# eBox_LCD.net
KiCad netlist of a schematic drawn in Altium Designer
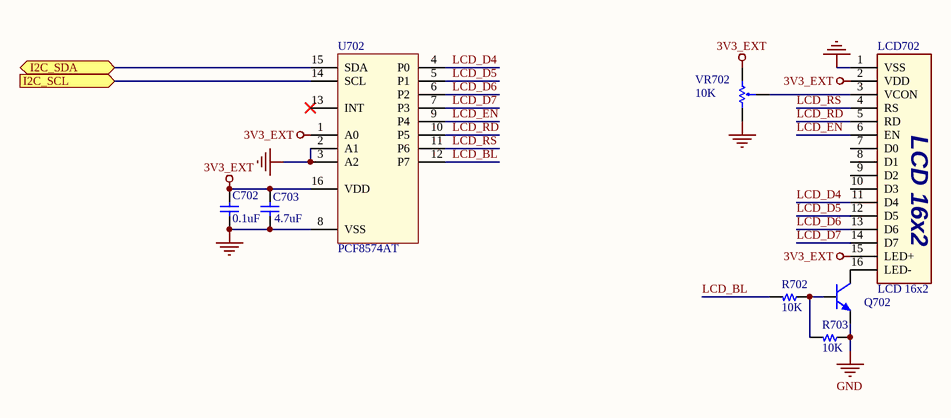
[diagram p0: eBox_LCD.SchDoc]

(export (version "E")
  (design (tool "Eeschema 10.0.6"))
  (components
    (comp (ref "C702")
      (value "0.1uF")
      (footprint "C 0603")
      (description "CAP CER 0.1UF 50V X7R 0603")
      (libsource (lib "chipfc_altium_libs") (part "Capacitor NP"))
    )
    (comp (ref "C703")
      (value "4.7uF")
      (footprint "C 0603")
      (description "CAP CER 4.7UF 50V X7R 0603")
      (libsource (lib "chipfc_altium_libs") (part "Capacitor NP"))
    )
    (comp (ref "LCD702")
      (value "LCD 16x2")
      (footprint "LCD 1602A")
      (description "Character LCD 16x2")
      (libsource (lib "chipfc_altium_libs") (part "LCD 16x2"))
    )
    (comp (ref "Q702")
      (value "LMBT3904LT1G")
      (footprint "SOT-23")
      (description "TRANS NPN 40V 0.2A SMD SOT23-3")
      (libsource (lib "chipfc_altium_libs") (part "Transistor NPN"))
    )
    (comp (ref "R702")
      (value "10K")
      (footprint "R 0603")
      (description "RES SMD 10K OHM 1% 1/10W 0603")
      (libsource (lib "chipfc_altium_libs") (part "Resistor"))
    )
    (comp (ref "R703")
      (value "10K")
      (footprint "R 0603")
      (description "RES SMD 10K OHM 1% 1/10W 0603")
      (libsource (lib "chipfc_altium_libs") (part "Resistor"))
    )
    (comp (ref "U702")
      (value "PCF8574AT")
      (footprint "SO16/PCF8574AT")
      (description "Remote 8-bit I/O expander for I2C-bus with interrupt")
      (fields (field (name "PART NO") "PCF8574AT/3"))
      (libsource (lib "chipfc_altium_libs") (part "PCF8574AT"))
    )
    (comp (ref "VR702")
      (value "10K")
      (footprint "R VAR A 3D")
      (description "Resistor Variable")
      (libsource (lib "chipfc_altium_libs") (part "Resistor Variable"))
    )
  )
  (nets
    (net (code "1") (name "/I2C_SCL") (class "Default")
      (node (ref "U702") (pin "14") (pinfunction "SCL_14") (pintype "passive"))
    )
    (net (code "2") (name "/I2C_SDA") (class "Default")
      (node (ref "U702") (pin "15") (pinfunction "SDA_15") (pintype "passive"))
    )
    (net (code "3") (name "/LCD_BL") (class "Default")
      (node (ref "R702") (pin "2") (pinfunction "2_2") (pintype "passive"))
      (node (ref "U702") (pin "12") (pinfunction "P7_12") (pintype "passive"))
    )
    (net (code "4") (name "/LCD_D4") (class "Default")
      (node (ref "LCD702") (pin "11") (pinfunction "D4_11") (pintype "passive"))
      (node (ref "U702") (pin "4") (pinfunction "P0_4") (pintype "passive"))
    )
    (net (code "5") (name "/LCD_D5") (class "Default")
      (node (ref "LCD702") (pin "12") (pinfunction "D5_12") (pintype "passive"))
      (node (ref "U702") (pin "5") (pinfunction "P1_5") (pintype "passive"))
    )
    (net (code "6") (name "/LCD_D6") (class "Default")
      (node (ref "LCD702") (pin "13") (pinfunction "D6_13") (pintype "passive"))
      (node (ref "U702") (pin "6") (pinfunction "P2_6") (pintype "passive"))
    )
    (net (code "7") (name "/LCD_D7") (class "Default")
      (node (ref "LCD702") (pin "14") (pinfunction "D7_14") (pintype "passive"))
      (node (ref "U702") (pin "7") (pinfunction "P3_7") (pintype "passive"))
    )
    (net (code "8") (name "/LCD_EN") (class "Default")
      (node (ref "LCD702") (pin "6") (pinfunction "EN_6") (pintype "passive"))
      (node (ref "U702") (pin "9") (pinfunction "P4_9") (pintype "passive"))
    )
    (net (code "9") (name "/LCD_RD") (class "Default")
      (node (ref "LCD702") (pin "5") (pinfunction "RD_5") (pintype "passive"))
      (node (ref "U702") (pin "10") (pinfunction "P5_10") (pintype "passive"))
    )
    (net (code "10") (name "/LCD_RS") (class "Default")
      (node (ref "LCD702") (pin "4") (pinfunction "RS_4") (pintype "passive"))
      (node (ref "U702") (pin "11") (pinfunction "P6_11") (pintype "passive"))
    )
    (net (code "11") (name "3V3_EXT") (class "Default")
      (node (ref "C702") (pin "1") (pinfunction "1_1") (pintype "passive"))
      (node (ref "C703") (pin "1") (pinfunction "1_1") (pintype "passive"))
      (node (ref "LCD702") (pin "15") (pinfunction "LED+_15") (pintype "passive"))
      (node (ref "LCD702") (pin "2") (pinfunction "VDD_2") (pintype "passive"))
      (node (ref "U702") (pin "1") (pinfunction "A0_1") (pintype "passive"))
      (node (ref "U702") (pin "16") (pinfunction "VDD_16") (pintype "passive"))
      (node (ref "VR702") (pin "1") (pinfunction "1_1") (pintype "passive"))
    )
    (net (code "12") (name "GND") (class "Default")
      (node (ref "C702") (pin "2") (pinfunction "2_2") (pintype "passive"))
      (node (ref "C703") (pin "2") (pinfunction "2_2") (pintype "passive"))
      (node (ref "LCD702") (pin "1") (pinfunction "VSS_1") (pintype "passive"))
      (node (ref "Q702") (pin "2") (pinfunction "E_2") (pintype "passive"))
      (node (ref "R703") (pin "1") (pinfunction "1_1") (pintype "passive"))
      (node (ref "U702") (pin "2") (pinfunction "A1_2") (pintype "passive"))
      (node (ref "U702") (pin "3") (pinfunction "A2_3") (pintype "passive"))
      (node (ref "U702") (pin "8") (pinfunction "VSS_8") (pintype "passive"))
      (node (ref "VR702") (pin "3") (pinfunction "3_3") (pintype "passive"))
    )
    (net (code "13") (name "Net-(LCD702-LED-)") (class "Default")
      (node (ref "LCD702") (pin "16") (pinfunction "LED-_16") (pintype "passive"))
      (node (ref "Q702") (pin "3") (pinfunction "C_3") (pintype "passive"))
    )
    (net (code "14") (name "Net-(LCD702-VCON)") (class "Default")
      (node (ref "LCD702") (pin "3") (pinfunction "VCON_3") (pintype "passive"))
      (node (ref "VR702") (pin "2") (pinfunction "2_2") (pintype "passive"))
    )
    (net (code "15") (name "Net-(Q702-B)") (class "Default")
      (node (ref "Q702") (pin "1") (pinfunction "B_1") (pintype "passive"))
      (node (ref "R702") (pin "1") (pinfunction "1_1") (pintype "passive"))
      (node (ref "R703") (pin "2") (pinfunction "2_2") (pintype "passive"))
    )
    (net (code "16") (name "unconnected-(LCD702-D0-Pad7)") (class "Default")
      (node (ref "LCD702") (pin "7") (pinfunction "D0_7") (pintype "passive"))
    )
    (net (code "17") (name "unconnected-(LCD702-D1-Pad8)") (class "Default")
      (node (ref "LCD702") (pin "8") (pinfunction "D1_8") (pintype "passive"))
    )
    (net (code "18") (name "unconnected-(LCD702-D2-Pad9)") (class "Default")
      (node (ref "LCD702") (pin "9") (pinfunction "D2_9") (pintype "passive"))
    )
    (net (code "19") (name "unconnected-(LCD702-D3-Pad10)") (class "Default")
      (node (ref "LCD702") (pin "10") (pinfunction "D3_10") (pintype "passive"))
    )
    (net (code "20") (name "unconnected-(U702-INT-Pad13)") (class "Default")
      (node (ref "U702") (pin "13") (pinfunction "INT_13") (pintype "passive+no_connect"))
    )
  )
)
